# Experimento.net
KiCad netlist of a schematic drawn in EAGLE
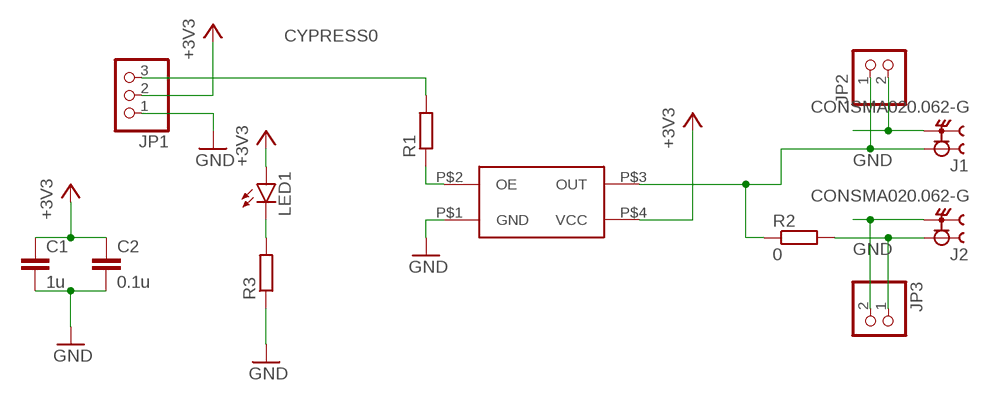
[diagram p0: schematic, sheet 1]

(export (version "E")
  (design (tool "Eeschema 10.0.6"))
  (components
    (comp (ref "C1")
      (value "1u")
      (footprint "eagle-import:C0805")
      (libsource (lib "eagle-import") (part "C-EUC0805"))
    )
    (comp (ref "C2")
      (value "0.1u")
      (footprint "eagle-import:C0805")
      (libsource (lib "eagle-import") (part "C-EUC0805"))
    )
    (comp (ref "J1")
      (value "CONSMA020.062-G")
      (footprint "eagle-import:LINX_CONSMA020.062-G")
      (fields
        (field (name "DIGI-KEY_PART_NUMBER") "343-CONSMA020.062-G-ND")
        (field (name "MF") "Linx Technologies")
      )
      (libsource (lib "eagle-import") (part "CONSMA020.062-G"))
    )
    (comp (ref "J2")
      (value "CONSMA020.062-G")
      (footprint "eagle-import:LINX_CONSMA020.062-G")
      (fields
        (field (name "DIGI-KEY_PART_NUMBER") "343-CONSMA020.062-G-ND")
        (field (name "MF") "Linx Technologies")
      )
      (libsource (lib "eagle-import") (part "CONSMA020.062-G"))
    )
    (comp (ref "JP1")
      (value "PINHD-1X3")
      (footprint "eagle-import:1X03")
      (libsource (lib "eagle-import") (part "PINHD-1X3"))
    )
    (comp (ref "JP2")
      (value "PINHD-1X2M")
      (footprint "eagle-import:1X02M")
      (libsource (lib "eagle-import") (part "PINHD-1X2M"))
    )
    (comp (ref "JP3")
      (value "PINHD-1X2M")
      (footprint "eagle-import:1X02M")
      (libsource (lib "eagle-import") (part "PINHD-1X2M"))
    )
    (comp (ref "LED1")
      (value "LEDSML0603")
      (footprint "eagle-import:SML0603")
      (libsource (lib "eagle-import") (part "LEDSML0603"))
    )
    (comp (ref "R1")
      (value "R-EU_R0603")
      (footprint "eagle-import:R0603")
      (libsource (lib "eagle-import") (part "R-EU_R0603"))
    )
    (comp (ref "R2")
      (value "0")
      (footprint "eagle-import:R1206")
      (libsource (lib "eagle-import") (part "R-EU_R1206"))
    )
    (comp (ref "R3")
      (value "R-EU_R0805")
      (footprint "eagle-import:R0805")
      (libsource (lib "eagle-import") (part "R-EU_R0805"))
    )
    (comp (ref "U$1")
      (value "732-XG1000CA100CBL3")
      (footprint "eagle-import:732-XG1000CA100CBL3")
      (libsource (lib "eagle-import") (part "732-XG1000CA100CBL3"))
    )
  )
  (nets
    (net (code "1") (name "+3V3") (class "Default")
      (node (ref "C1") (pin "1") (pinfunction "1_1") (pintype "passive"))
      (node (ref "C2") (pin "1") (pinfunction "1_1") (pintype "passive"))
      (node (ref "JP1") (pin "2") (pinfunction "2_2") (pintype "passive"))
      (node (ref "LED1") (pin "A") (pinfunction "A_A") (pintype "passive"))
      (node (ref "U$1") (pin "P$4") (pinfunction "VCC_P$4") (pintype "bidirectional"))
    )
    (net (code "2") (name "/CYPRESS0") (class "Default")
      (node (ref "JP1") (pin "3") (pinfunction "3_3") (pintype "passive"))
      (node (ref "R1") (pin "2") (pinfunction "2_2") (pintype "passive"))
    )
    (net (code "3") (name "GND") (class "Default")
      (node (ref "C1") (pin "2") (pinfunction "2_2") (pintype "passive"))
      (node (ref "C2") (pin "2") (pinfunction "2_2") (pintype "passive"))
      (node (ref "J1") (pin "S1") (pinfunction "2_S1") (pintype "passive"))
      (node (ref "J1") (pin "S2") (pinfunction "2_S2") (pintype "passive"))
      (node (ref "J1") (pin "S3") (pinfunction "2_S3") (pintype "passive"))
      (node (ref "J1") (pin "S4") (pinfunction "2_S4") (pintype "passive"))
      (node (ref "J2") (pin "S1") (pinfunction "2_S1") (pintype "passive"))
      (node (ref "J2") (pin "S2") (pinfunction "2_S2") (pintype "passive"))
      (node (ref "J2") (pin "S3") (pinfunction "2_S3") (pintype "passive"))
      (node (ref "J2") (pin "S4") (pinfunction "2_S4") (pintype "passive"))
      (node (ref "JP1") (pin "1") (pinfunction "1_1") (pintype "passive"))
      (node (ref "JP2") (pin "2") (pinfunction "2_2") (pintype "passive"))
      (node (ref "JP3") (pin "2") (pinfunction "2_2") (pintype "passive"))
      (node (ref "R3") (pin "1") (pinfunction "1_1") (pintype "passive"))
      (node (ref "U$1") (pin "P$1") (pinfunction "GND_P$1") (pintype "bidirectional"))
    )
    (net (code "4") (name "Net-(J2-Pad1)") (class "Default")
      (node (ref "J2") (pin "1") (pinfunction "1_1") (pintype "passive"))
      (node (ref "JP3") (pin "1") (pinfunction "1_1") (pintype "passive"))
      (node (ref "R2") (pin "2") (pinfunction "2_2") (pintype "passive"))
    )
    (net (code "5") (name "Net-(LED1-PadC)") (class "Default")
      (node (ref "LED1") (pin "C") (pinfunction "C_C") (pintype "passive"))
      (node (ref "R3") (pin "2") (pinfunction "2_2") (pintype "passive"))
    )
    (net (code "6") (name "Net-(U$1-OE)") (class "Default")
      (node (ref "R1") (pin "1") (pinfunction "1_1") (pintype "passive"))
      (node (ref "U$1") (pin "P$2") (pinfunction "OE_P$2") (pintype "bidirectional"))
    )
    (net (code "7") (name "Net-(U$1-OUT)") (class "Default")
      (node (ref "J1") (pin "1") (pinfunction "1_1") (pintype "passive"))
      (node (ref "JP2") (pin "1") (pinfunction "1_1") (pintype "passive"))
      (node (ref "R2") (pin "1") (pinfunction "1_1") (pintype "passive"))
      (node (ref "U$1") (pin "P$3") (pinfunction "OUT_P$3") (pintype "bidirectional"))
    )
  )
)
